# IO_Bus_Switch.net
KiCad netlist of a schematic drawn in Altium Designer
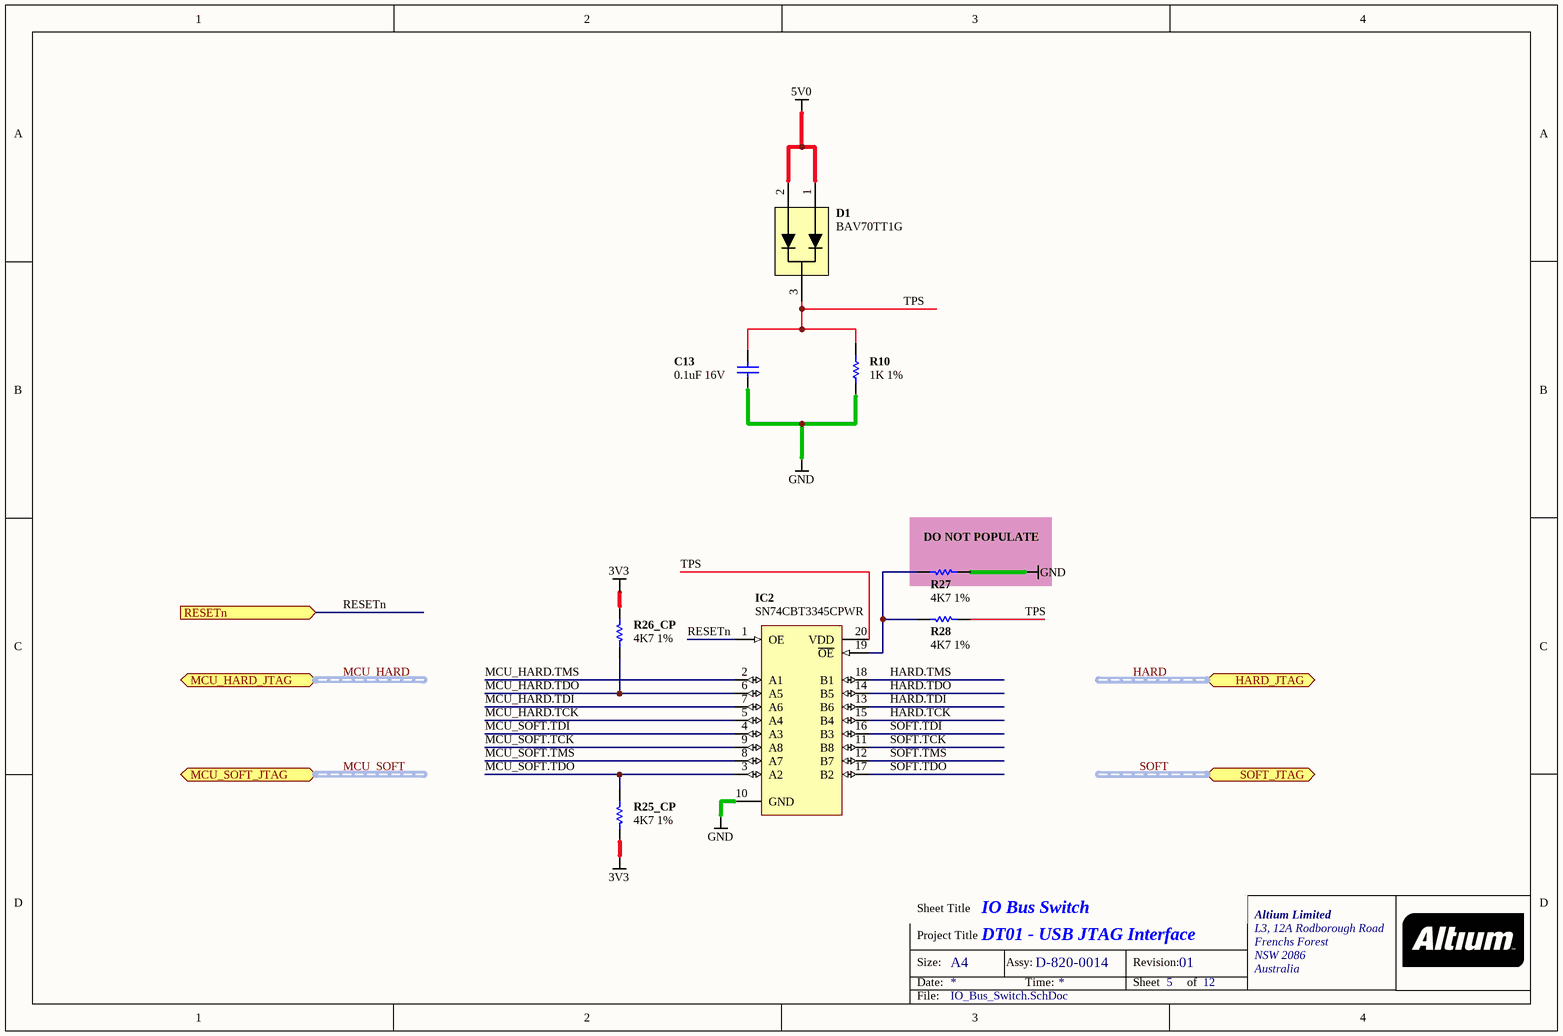
[diagram p0: IO_Bus_Switch.SchDoc]

(export (version "E")
  (design (tool "Eeschema 10.0.6"))
  (components
    (comp (ref "C13")
      (value "0.1uF 16V")
      (footprint "CAPC1005-STAR")
      (description "Capacitor, Ceramic, 0.1uF 10% 16V 0402 (1005) X7R")
      (fields (field (name "TOLERANCE") "10 %"))
      (libsource (lib "AltiumDesignLibrary") (part "CAP-NP"))
    )
    (comp (ref "D1")
      (value "BAV70TT1G")
      (footprint "SOT95P230-3")
      (description "Dual Switching Diode")
      (libsource (lib "AltiumDesignLibrary") (part "BAV70"))
    )
    (comp (ref "IC2")
      (value "SN74CBT3345CPWR")
      (footprint "TSOP65P650-20")
      (description "SN74CBT3345CPWR; HIGH SPEED 8-BIT BUS SWITCH")
      (libsource (lib "AltiumDesignLibrary") (part "SN74CBT3345PWLE"))
    )
    (comp (ref "R10")
      (value "1K 1%")
      (footprint "RESC1005-STAR")
      (description "Resistor, 1K 1% 0402 (1005)")
      (fields (field (name "TOLERANCE") "1 %"))
      (libsource (lib "AltiumDesignLibrary") (part "RES"))
    )
    (comp (ref "R25_CP")
      (value "4K7 1%")
      (footprint "RESC1005-STAR")
      (description "Resistor, 4K7 1% 0402 (1005)")
      (fields (field (name "TOLERANCE") "1 %"))
      (libsource (lib "AltiumDesignLibrary") (part "RES"))
    )
    (comp (ref "R26_CP")
      (value "4K7 1%")
      (footprint "RESC1005-STAR")
      (description "Resistor, 4K7 1% 0402 (1005)")
      (fields (field (name "TOLERANCE") "1 %"))
      (libsource (lib "AltiumDesignLibrary") (part "RES"))
    )
    (comp (ref "R27")
      (value "4K7 1%")
      (footprint "RESC1005-STAR")
      (description "Resistor, 4K7 1% 0402 (1005)")
      (fields (field (name "TOLERANCE") "1 %"))
      (libsource (lib "") (part "RES_1"))
    )
    (comp (ref "R28")
      (value "4K7 1%")
      (footprint "RESC1005-STAR")
      (description "Resistor, 4K7 1% 0402 (1005)")
      (fields (field (name "TOLERANCE") "1 %"))
      (libsource (lib "") (part "RES_1"))
    )
  )
  (nets
    (net (code "5") (name "/HARD.TCK") (class "Default")
      (node (ref "IC2") (pin "15") (pinfunction "B4_15") (pintype "bidirectional"))
    )
    (net (code "6") (name "/HARD.TDI") (class "Default")
      (node (ref "IC2") (pin "13") (pinfunction "B6_13") (pintype "bidirectional"))
    )
    (net (code "7") (name "/HARD.TDO") (class "Default")
      (node (ref "IC2") (pin "14") (pinfunction "B5_14") (pintype "bidirectional"))
    )
    (net (code "8") (name "/HARD.TMS") (class "Default")
      (node (ref "IC2") (pin "18") (pinfunction "B1_18") (pintype "bidirectional"))
    )
    (net (code "9") (name "/MCU_HARD.TCK") (class "Default")
      (node (ref "IC2") (pin "5") (pinfunction "A4_5") (pintype "bidirectional"))
    )
    (net (code "10") (name "/MCU_HARD.TDI") (class "Default")
      (node (ref "IC2") (pin "7") (pinfunction "A6_7") (pintype "bidirectional"))
    )
    (net (code "11") (name "/MCU_HARD.TDO") (class "Default")
      (node (ref "IC2") (pin "6") (pinfunction "A5_6") (pintype "bidirectional"))
      (node (ref "R26_CP") (pin "1") (pinfunction "1_1") (pintype "passive"))
    )
    (net (code "12") (name "/MCU_HARD.TMS") (class "Default")
      (node (ref "IC2") (pin "2") (pinfunction "A1_2") (pintype "bidirectional"))
    )
    (net (code "13") (name "/MCU_SOFT.TCK") (class "Default")
      (node (ref "IC2") (pin "9") (pinfunction "A8_9") (pintype "bidirectional"))
    )
    (net (code "14") (name "/MCU_SOFT.TDI") (class "Default")
      (node (ref "IC2") (pin "4") (pinfunction "A3_4") (pintype "bidirectional"))
    )
    (net (code "15") (name "/MCU_SOFT.TDO") (class "Default")
      (node (ref "IC2") (pin "3") (pinfunction "A2_3") (pintype "bidirectional"))
      (node (ref "R25_CP") (pin "1") (pinfunction "1_1") (pintype "passive"))
    )
    (net (code "16") (name "/MCU_SOFT.TMS") (class "Default")
      (node (ref "IC2") (pin "8") (pinfunction "A7_8") (pintype "bidirectional"))
    )
    (net (code "17") (name "/RESETn") (class "Default")
      (node (ref "IC2") (pin "1") (pinfunction "OE_1") (pintype "input"))
    )
    (net (code "18") (name "/SOFT.TCK") (class "Default")
      (node (ref "IC2") (pin "11") (pinfunction "B8_11") (pintype "bidirectional"))
    )
    (net (code "19") (name "/SOFT.TDI") (class "Default")
      (node (ref "IC2") (pin "16") (pinfunction "B3_16") (pintype "bidirectional"))
    )
    (net (code "20") (name "/SOFT.TDO") (class "Default")
      (node (ref "IC2") (pin "17") (pinfunction "B2_17") (pintype "bidirectional"))
    )
    (net (code "21") (name "/SOFT.TMS") (class "Default")
      (node (ref "IC2") (pin "12") (pinfunction "B7_12") (pintype "bidirectional"))
    )
    (net (code "22") (name "/TPS") (class "Default")
      (node (ref "C13") (pin "1") (pinfunction "1_1") (pintype "passive"))
      (node (ref "D1") (pin "3") (pintype "passive"))
      (node (ref "IC2") (pin "20") (pinfunction "VDD_20") (pintype "power_in"))
      (node (ref "R10") (pin "1") (pinfunction "1_1") (pintype "passive"))
      (node (ref "R28") (pin "1") (pinfunction "1_1") (pintype "passive"))
    )
    (net (code "27") (name "3V3") (class "Default")
      (node (ref "R25_CP") (pin "2") (pinfunction "2_2") (pintype "passive"))
      (node (ref "R26_CP") (pin "2") (pinfunction "2_2") (pintype "passive"))
    )
    (net (code "28") (name "5V0") (class "Default")
      (node (ref "D1") (pin "1") (pintype "passive"))
      (node (ref "D1") (pin "2") (pintype "passive"))
    )
    (net (code "29") (name "GND") (class "Default")
      (node (ref "C13") (pin "2") (pinfunction "2_2") (pintype "passive"))
      (node (ref "IC2") (pin "10") (pinfunction "GND_10") (pintype "power_in"))
      (node (ref "R10") (pin "2") (pinfunction "2_2") (pintype "passive"))
      (node (ref "R27") (pin "1") (pinfunction "1_1") (pintype "passive"))
    )
    (net (code "30") (name "Net-(IC2-~{OE})") (class "Default")
      (node (ref "IC2") (pin "19") (pinfunction "~{OE}_19") (pintype "input"))
      (node (ref "R27") (pin "2") (pinfunction "2_2") (pintype "passive"))
      (node (ref "R28") (pin "2") (pinfunction "2_2") (pintype "passive"))
    )
  )
)
